# Lenobitech_Schematic.net
KiCad netlist of a schematic drawn in Altium Designer
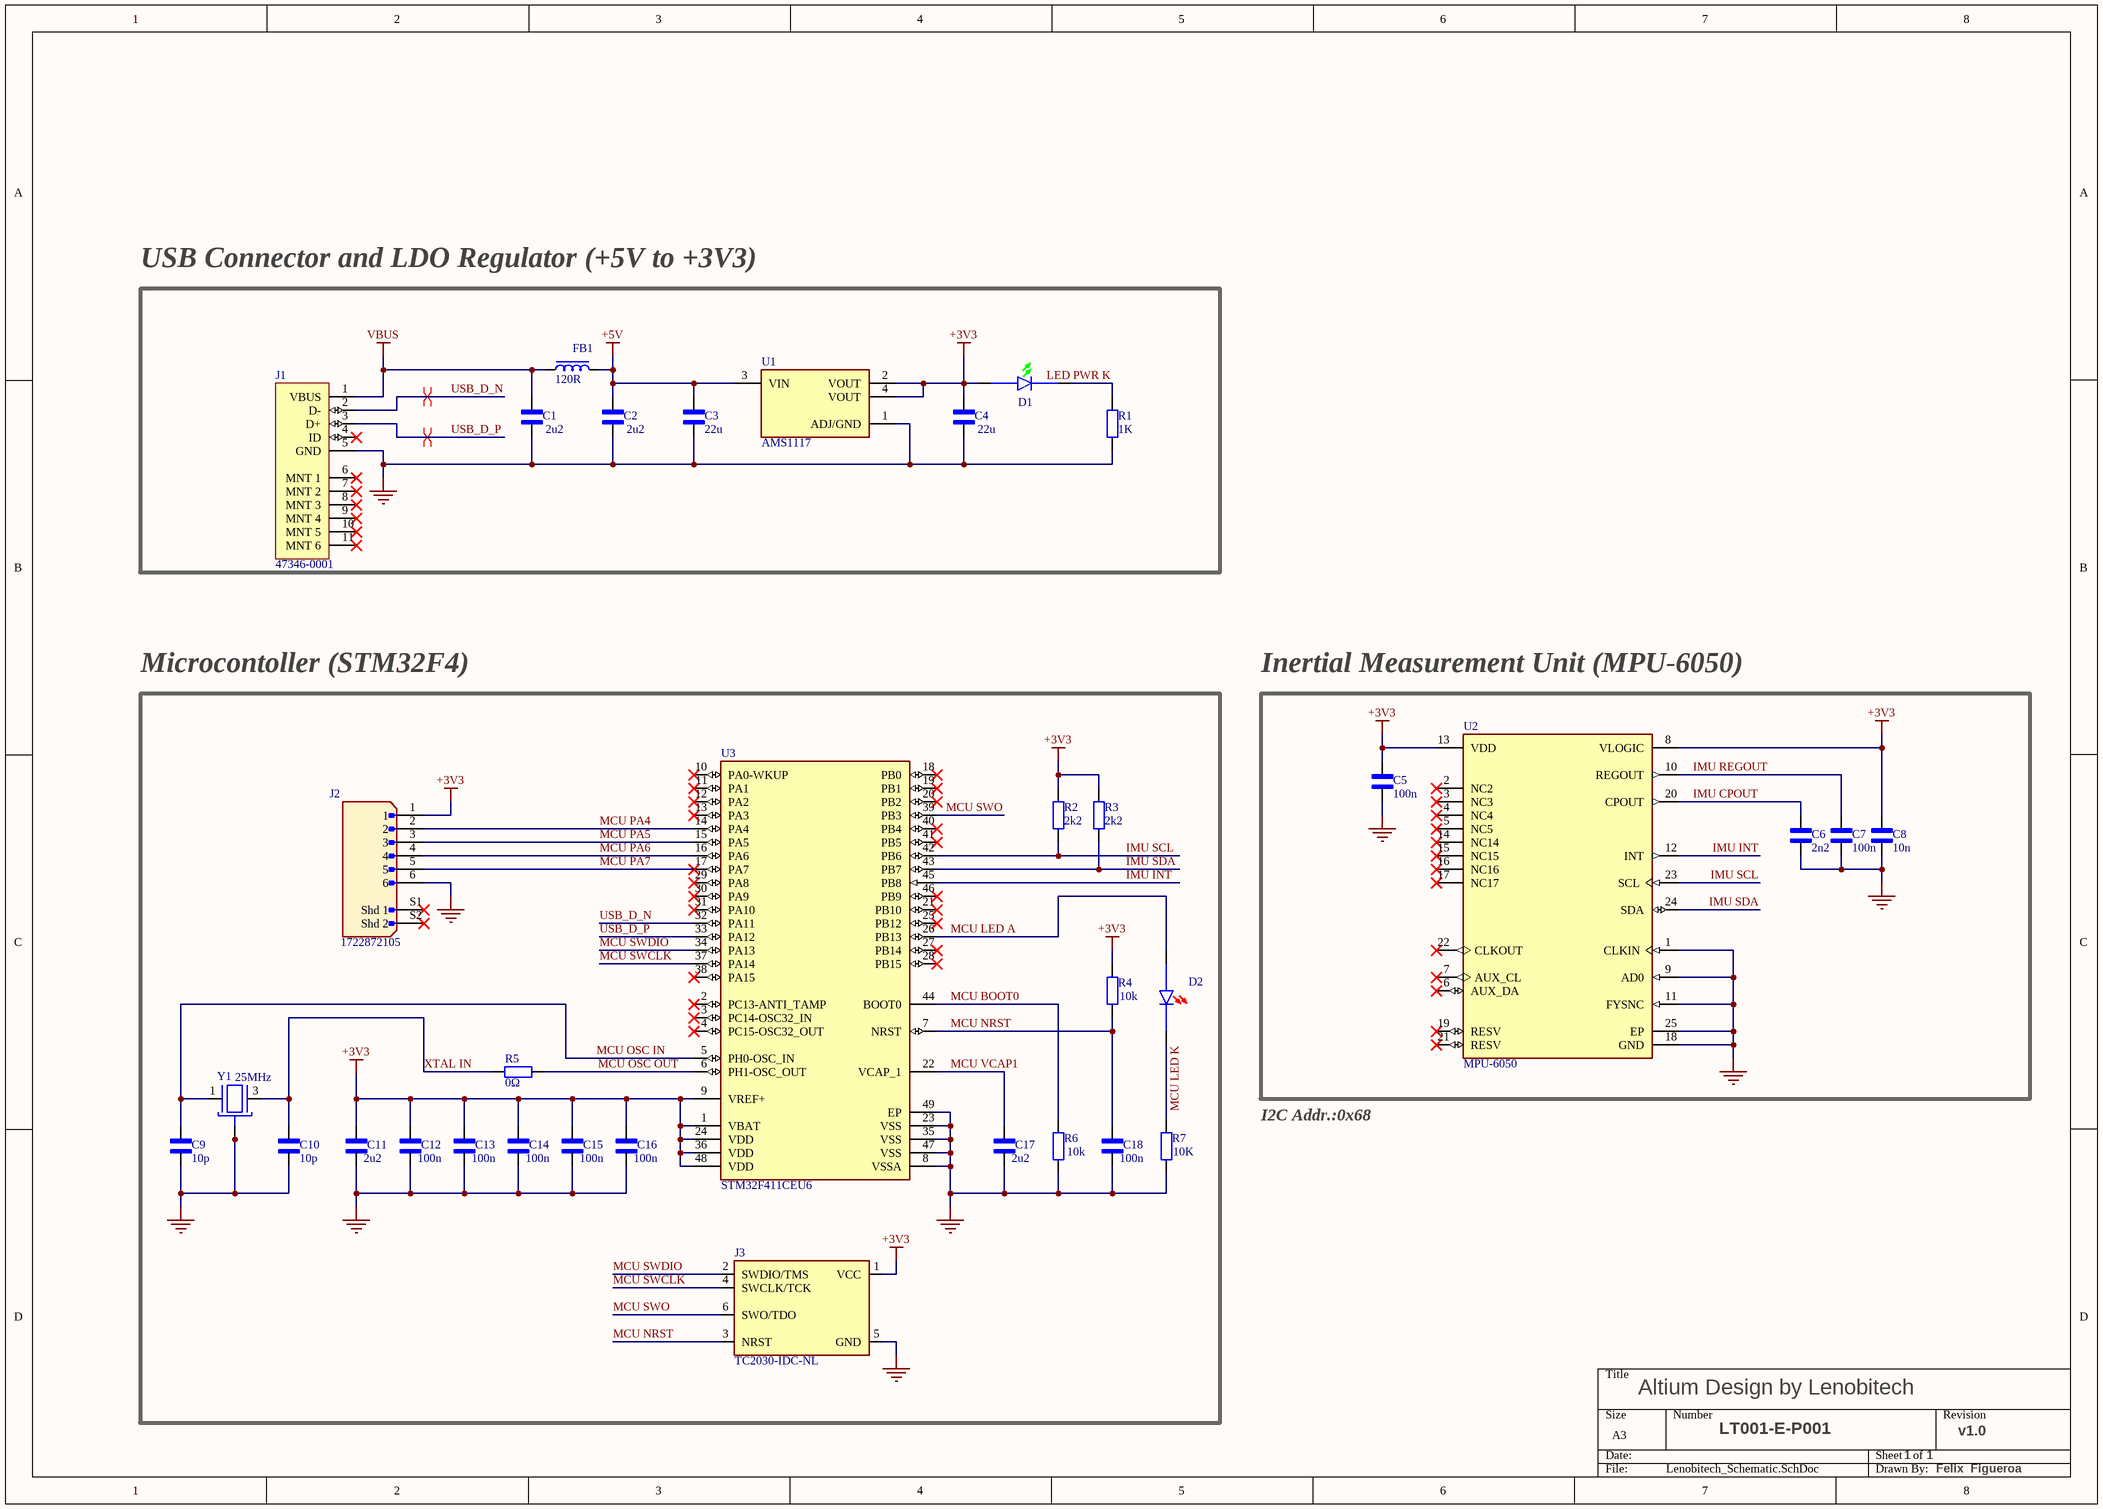
[diagram p0: Lenobitech_Schematic.SchDoc]

(export (version "E")
  (design (tool "Eeschema 10.0.6"))
  (components
    (comp (ref "C1")
      (value "2u2")
      (footprint "CAPC1608X90N")
      (description "C0603C225K4PACTU\r\n2.2碌F 卤10% 16V Ceramic Capacitor X5R 0603 _1608 Metric_")
      (fields (field (name "MF") "KEMET") (field (name "MP") "C0603C225K4PACTU"))
      (libsource (lib "Schlib_Lenobitech") (part "C0603_16V"))
    )
    (comp (ref "C2")
      (value "2u2")
      (footprint "CAPC1608X90N")
      (description "C0603C225K4PACTU\r\n2.2碌F 卤10% 16V Ceramic Capacitor X5R 0603 _1608 Metric_")
      (fields (field (name "MF") "KEMET") (field (name "MP") "C0603C225K4PACTU"))
      (libsource (lib "Schlib_Lenobitech") (part "CAP_0603_16V"))
    )
    (comp (ref "C3")
      (value "22u")
      (footprint "CAPC2012X145N")
      (description "C0805C226M8PAC7800\r\n22碌F 卤20% 16V Ceramic Capacitor X5R 0805 _2012 Metric_")
      (fields (field (name "MP") "C0805C226M8PAC7800") (field (name "DIGI-KEY_PART_NUMBER") "399-12069-1-ND"))
      (libsource (lib "Schlib_Lenobitech") (part "CAP_0805_16V"))
    )
    (comp (ref "C4")
      (value "22u")
      (footprint "CAPC2012X145N")
      (description "C0805C226M8PAC7800\r\n22碌F 卤20% 16V Ceramic Capacitor X5R 0805 _2012 Metric_")
      (fields (field (name "MF") "KEMET") (field (name "MP") "C0805C226M8PAC7800"))
      (libsource (lib "Schlib_Lenobitech") (part "CAP_0805_16V"))
    )
    (comp (ref "C5")
      (value "100n")
      (footprint "CAPC1005X55N")
      (description "C0402C104K4RAC7411_KEMET\r\n0.1碌F 卤10% 16V Ceramic Capacitor X7R 0402 (1005 Metric)")
      (fields (field (name "MP") "C0402C104K4RAC7411") (field (name "MF") "KEMET"))
      (libsource (lib "Schlib_Lenobitech") (part "CAP_0402_16V"))
    )
    (comp (ref "C6")
      (value "2n2")
      (footprint "CAPC1005X55N")
      (description "C0402C104K4RAC7411_KEMET\r\n0.1碌F 卤10% 16V Ceramic Capacitor X7R 0402 (1005 Metric)")
      (fields (field (name "MP") "C0402C104K4RAC7411") (field (name "MF") "KEMET"))
      (libsource (lib "") (part "CAP_0402_16V_1"))
    )
    (comp (ref "C7")
      (value "100n")
      (footprint "CAPC1005X55N")
      (description "C0402C104K4RAC7411_KEMET\r\n0.1碌F 卤10% 16V Ceramic Capacitor X7R 0402 (1005 Metric)")
      (fields (field (name "MP") "C0402C104K4RAC7411") (field (name "MF") "KEMET"))
      (libsource (lib "") (part "CAP_0402_16V_1"))
    )
    (comp (ref "C8")
      (value "10n")
      (footprint "CAPC1005X55N")
      (description "C0402C104K4RAC7411_KEMET\r\n0.1碌F 卤10% 16V Ceramic Capacitor X7R 0402 (1005 Metric)")
      (fields (field (name "MP") "C0402C104K4RAC7411") (field (name "MF") "KEMET"))
      (libsource (lib "") (part "CAP_0402_16V_1"))
    )
    (comp (ref "C9")
      (value "10p")
      (footprint "CAPC1005X55N")
      (description "C0402C104K4RAC7411_KEMET\r\n0.1碌F 卤10% 16V Ceramic Capacitor X7R 0402 (1005 Metric)")
      (fields (field (name "MP") "C0402C104K4RAC7411") (field (name "MF") "KEMET"))
      (libsource (lib "Schlib_Lenobitech") (part "CAP_0402_16V"))
    )
    (comp (ref "C10")
      (value "10p")
      (footprint "CAPC1005X55N")
      (description "C0402C104K4RAC7411_KEMET\r\n0.1碌F 卤10% 16V Ceramic Capacitor X7R 0402 (1005 Metric)")
      (fields (field (name "MP") "C0402C104K4RAC7411") (field (name "MF") "KEMET"))
      (libsource (lib "Schlib_Lenobitech") (part "CAP_0402_16V"))
    )
    (comp (ref "C11")
      (value "2u2")
      (footprint "CAPC1608X90N")
      (description "C0603C225K4PACTU\r\n2.2碌F 卤10% 16V Ceramic Capacitor X5R 0603 _1608 Metric_")
      (fields (field (name "MF") "KEMET") (field (name "MP") "C0603C225K4PACTU"))
      (libsource (lib "Schlib_Lenobitech") (part "C0603_16V"))
    )
    (comp (ref "C12")
      (value "100n")
      (footprint "CAPC1005X55N")
      (description "C0402C104K4RAC7411_KEMET\r\n0.1碌F 卤10% 16V Ceramic Capacitor X7R 0402 (1005 Metric)")
      (fields (field (name "MP") "C0402C104K4RAC7411") (field (name "MF") "KEMET"))
      (libsource (lib "Schlib_Lenobitech") (part "C0402_16V"))
    )
    (comp (ref "C13")
      (value "100n")
      (footprint "CAPC1005X55N")
      (description "C0402C104K4RAC7411_KEMET\r\n0.1碌F 卤10% 16V Ceramic Capacitor X7R 0402 (1005 Metric)")
      (fields (field (name "MP") "C0402C104K4RAC7411") (field (name "MF") "KEMET"))
      (libsource (lib "Schlib_Lenobitech") (part "C0402_16V"))
    )
    (comp (ref "C14")
      (value "100n")
      (footprint "CAPC1005X55N")
      (description "C0402C104K4RAC7411_KEMET\r\n0.1碌F 卤10% 16V Ceramic Capacitor X7R 0402 (1005 Metric)")
      (fields (field (name "MP") "C0402C104K4RAC7411") (field (name "MF") "KEMET"))
      (libsource (lib "Schlib_Lenobitech") (part "C0402_16V"))
    )
    (comp (ref "C15")
      (value "100n")
      (footprint "CAPC1005X55N")
      (description "C0402C104K4RAC7411_KEMET\r\n0.1碌F 卤10% 16V Ceramic Capacitor X7R 0402 (1005 Metric)")
      (fields (field (name "MP") "C0402C104K4RAC7411") (field (name "MF") "KEMET"))
      (libsource (lib "Schlib_Lenobitech") (part "C0402_16V"))
    )
    (comp (ref "C16")
      (value "100n")
      (footprint "CAPC1005X55N")
      (description "C0402C104K4RAC7411_KEMET\r\n0.1碌F 卤10% 16V Ceramic Capacitor X7R 0402 (1005 Metric)")
      (fields (field (name "MP") "C0402C104K4RAC7411") (field (name "MF") "KEMET"))
      (libsource (lib "Schlib_Lenobitech") (part "C0402_16V"))
    )
    (comp (ref "C17")
      (value "2u2")
      (footprint "CAPC1608X90N")
      (description "C0603C225K4PACTU\r\n2.2碌F 卤10% 16V Ceramic Capacitor X5R 0603 _1608 Metric_")
      (fields (field (name "MF") "KEMET") (field (name "MP") "C0603C225K4PACTU"))
      (libsource (lib "Schlib_Lenobitech") (part "C0603_16V"))
    )
    (comp (ref "C18")
      (value "100n")
      (footprint "CAPC1005X55N")
      (description "C0402C104K4RAC7411_KEMET\r\n0.1碌F 卤10% 16V Ceramic Capacitor X7R 0402 (1005 Metric)")
      (fields (field (name "MP") "C0402C104K4RAC7411") (field (name "MF") "KEMET"))
      (libsource (lib "Schlib_Lenobitech") (part "C0402_16V"))
    )
    (comp (ref "D1")
      (value "HSMS-C190")
      (footprint "LEDM1608X80")
      (description "Red 626nm LED Indication - Discrete 2.1V 0603 _1608 Metric_")
      (fields (field (name "MF") "Broadcom Limited"))
      (libsource (lib "Schlib_Lenobitech") (part "HSMS-C190"))
    )
    (comp (ref "D2")
      (value "HSMS-C190_1")
      (footprint "LEDM1608X80")
      (description "Red 626nm LED Indication - Discrete 2.1V 0603 _1608 Metric_")
      (fields (field (name "MP") "HSMS-C190") (field (name "MF") "Broadcom Limited"))
      (libsource (lib "Schlib_Lenobitech") (part "HSMS-C190_RD"))
    )
    (comp (ref "FB1")
      (value "120R")
      (footprint "PcbLib_Lenobitech:BEADC1608X75N")
      (description "1 kOhms @ 100MHz 1 G眉莽 Hatt谋 Ferrit Boncuk 0603 (1608 Metrik) 800mA 230mOhm")
      (fields (field (name "MP") "BLM18KG102WH1D") (field (name "MF") "Murata"))
      (libsource (lib "Schlib_Lenobitech") (part "BLM18KG102WH1D"))
    )
    (comp (ref "J1")
      (value "47346-0001")
      (footprint "PcbLib_Lenobitech:MOLEX_47346-0001")
      (description "USB Connectors MICRO USB B RECPT BTTM MOUNT ASSY")
      (fields (field (name "MF") "Molex"))
      (libsource (lib "Schlib_Lenobitech") (part "47346-0001"))
    )
    (comp (ref "J2")
      (value "1722872105")
      (footprint "JST_SM06B-SRSS-TB(LF)(SN)")
      (description "Connector Header Surface Mount, Right Angle 6 position 0.039\" (1.00mm)")
      (libsource (lib "Schlib_Lenobitech") (part "SM06B-SRSS-TB"))
    )
    (comp (ref "J3")
      (value "TC2030-IDC-NL")
      (footprint "TAG_TC2030-IDC-NL")
      (description "CABLE ADAPTER 6 POS")
      (libsource (lib "Schlib_Lenobitech") (part "TC2030-IDC-NL"))
    )
    (comp (ref "R1")
      (value "1K")
      (footprint "RESC1005X37N")
      (description "AC0402 10K 5% 0,063W AUTOMO")
      (fields (field (name "MP") "AC0402JR-0710KL") (field (name "Comment") "RES_0402"))
      (libsource (lib "Schlib_Lenobitech") (part "RES_0402"))
    )
    (comp (ref "R2")
      (value "2k2")
      (footprint "RESC1005X37N")
      (description "AC0402 10K 5% 0,063W AUTOMO")
      (fields (field (name "MP") "AC0402JR-0710KL") (field (name "Comment") "RES_0402"))
      (libsource (lib "Schlib_Lenobitech") (part "RES_0402"))
    )
    (comp (ref "R3")
      (value "2k2")
      (footprint "RESC1005X37N")
      (description "AC0402 10K 5% 0,063W AUTOMO")
      (fields (field (name "MP") "AC0402JR-0710KL") (field (name "Comment") "RES_0402"))
      (libsource (lib "Schlib_Lenobitech") (part "RES_0402"))
    )
    (comp (ref "R4")
      (value "10k")
      (footprint "RESC1005X37N")
      (description "AC0402 10K 5% 0,063W AUTOMO")
      (fields (field (name "MP") "AC0402JR-0710KL") (field (name "Comment") "RES_0402"))
      (libsource (lib "Schlib_Lenobitech") (part "RES_0402"))
    )
    (comp (ref "R5")
      (value "0Ω")
      (footprint "RESC1005X37N")
      (description "AC0402 10K 5% 0,063W AUTOMO")
      (fields (field (name "MP") "AC0402JR-0710KL") (field (name "Comment") "RES_0402"))
      (libsource (lib "") (part "RES_0402_1"))
    )
    (comp (ref "R6")
      (value "10k")
      (footprint "RESC1005X37N")
      (description "AC0402 10K 5% 0,063W AUTOMO")
      (fields (field (name "MP") "AC0402JR-0710KL") (field (name "Comment") "RES_0402"))
      (libsource (lib "Schlib_Lenobitech") (part "RES_0402"))
    )
    (comp (ref "R7")
      (value "10K")
      (footprint "RESC1005X37N")
      (description "AC0402 10K 5% 0,063W AUTOMO")
      (fields (field (name "MP") "AC0402JR-0710KL") (field (name "Comment") "RES_0402"))
      (libsource (lib "") (part "RES_0402_2"))
    )
    (comp (ref "U1")
      (value "AMS1117")
      (footprint "SOT229P700X180-4N")
      (description "Sot223/Pkg 1-Amp 5-Volt Low Drop Out Voltage Regulatator")
      (libsource (lib "Schlib_Lenobitech") (part "AMS1117"))
    )
    (comp (ref "U2")
      (value "MPU-6050")
      (footprint "PcbLib_Lenobitech:IC_MPU6050")
      (fields (field (name "MP") "MPU6050"))
      (libsource (lib "Schlib_Lenobitech") (part "MPU6050"))
    )
    (comp (ref "U3")
      (value "STM32F411CEU6")
      (footprint "PcbLib_Lenobitech:QFN50P700X700X60-49N")
      (description "ARMÂ® CortexÂ®-M4 STM32F4 Microcontroller IC 32-Bit 100MHz 512KB (512K x 8) FLASH 48-UFQFPN (7x7)")
      (fields (field (name "MF") "STMicroelectronics"))
      (libsource (lib "Schlib_Lenobitech") (part "STM32F411CEU6"))
    )
    (comp (ref "Y1")
      (value "25MHz")
      (footprint "OSC_ABM3B-25.000MHZ-10-1-U-T")
      (description "25 MHz Â±10ppm Crystal 10pF 50 Ohms 4-SMD, No Lead")
      (fields (field (name "MF") "Abracon") (field (name "MP") "ABM3B-25.000MHZ-10-1-U-T"))
      (libsource (lib "Schlib_Lenobitech") (part "ABM3B-25.000MHZ-10-1-U-T"))
    )
  )
  (nets
    (net (code "1") (name "+3V3") (class "Default")
      (node (ref "C11") (pin "2") (pinfunction "2_2") (pintype "passive"))
      (node (ref "C12") (pin "2") (pinfunction "2_2") (pintype "passive"))
      (node (ref "C13") (pin "2") (pinfunction "2_2") (pintype "passive"))
      (node (ref "C14") (pin "2") (pinfunction "2_2") (pintype "passive"))
      (node (ref "C15") (pin "2") (pinfunction "2_2") (pintype "passive"))
      (node (ref "C16") (pin "2") (pinfunction "2_2") (pintype "passive"))
      (node (ref "C4") (pin "2") (pinfunction "2_2") (pintype "passive"))
      (node (ref "C5") (pin "2") (pinfunction "2_2") (pintype "passive"))
      (node (ref "C8") (pin "1") (pinfunction "1_1") (pintype "passive"))
      (node (ref "D1") (pin "A") (pinfunction "A_A") (pintype "passive"))
      (node (ref "J2") (pin "1") (pinfunction "1_1") (pintype "passive"))
      (node (ref "J3") (pin "1") (pinfunction "VCC_1") (pintype "passive"))
      (node (ref "R2") (pin "2") (pinfunction "2_2") (pintype "passive"))
      (node (ref "R3") (pin "2") (pinfunction "2_2") (pintype "passive"))
      (node (ref "R4") (pin "2") (pinfunction "2_2") (pintype "passive"))
      (node (ref "U1") (pin "2") (pinfunction "VOUT_2") (pintype "passive"))
      (node (ref "U1") (pin "4") (pinfunction "VOUT_4") (pintype "passive"))
      (node (ref "U2") (pin "13") (pinfunction "VDD_13") (pintype "power_in"))
      (node (ref "U2") (pin "8") (pinfunction "VLOGIC_8") (pintype "power_in"))
      (node (ref "U3") (pin "1") (pinfunction "VBAT_1") (pintype "passive"))
      (node (ref "U3") (pin "24") (pinfunction "VDD_24") (pintype "passive"))
      (node (ref "U3") (pin "36") (pinfunction "VDD_36") (pintype "passive"))
      (node (ref "U3") (pin "48") (pinfunction "VDD_48") (pintype "passive"))
      (node (ref "U3") (pin "9") (pinfunction "VREF+_9") (pintype "passive"))
    )
    (net (code "2") (name "+5V") (class "Default")
      (node (ref "C2") (pin "2") (pinfunction "2_2") (pintype "passive"))
      (node (ref "C3") (pin "2") (pinfunction "2_2") (pintype "passive"))
      (node (ref "FB1") (pin "2") (pinfunction "2_2") (pintype "passive"))
      (node (ref "U1") (pin "3") (pinfunction "VIN_3") (pintype "passive"))
    )
    (net (code "3") (name "/IMU CPOUT") (class "Default")
      (node (ref "C6") (pin "1") (pinfunction "1_1") (pintype "passive"))
      (node (ref "U2") (pin "20") (pinfunction "CPOUT_20") (pintype "output"))
    )
    (net (code "4") (name "/IMU INT") (class "Default")
      (node (ref "U2") (pin "12") (pinfunction "INT_12") (pintype "output"))
      (node (ref "U3") (pin "45") (pinfunction "PB8_45") (pintype "input"))
    )
    (net (code "5") (name "/IMU REGOUT") (class "Default")
      (node (ref "C7") (pin "1") (pinfunction "1_1") (pintype "passive"))
      (node (ref "U2") (pin "10") (pinfunction "REGOUT_10") (pintype "output"))
    )
    (net (code "6") (name "/IMU SCL") (class "Default")
      (node (ref "R2") (pin "1") (pinfunction "1_1") (pintype "passive"))
      (node (ref "U2") (pin "23") (pinfunction "SCL_23") (pintype "input"))
      (node (ref "U3") (pin "42") (pinfunction "PB6_42") (pintype "bidirectional"))
    )
    (net (code "7") (name "/IMU SDA") (class "Default")
      (node (ref "R3") (pin "1") (pinfunction "1_1") (pintype "passive"))
      (node (ref "U2") (pin "24") (pinfunction "SDA_24") (pintype "bidirectional"))
      (node (ref "U3") (pin "43") (pinfunction "PB7_43") (pintype "bidirectional"))
    )
    (net (code "8") (name "/LED PWR K") (class "Default")
      (node (ref "D1") (pin "K") (pinfunction "K_K") (pintype "passive"))
      (node (ref "R1") (pin "2") (pinfunction "2_2") (pintype "passive"))
    )
    (net (code "9") (name "/MCU BOOT0") (class "Default")
      (node (ref "R6") (pin "2") (pinfunction "2_2") (pintype "passive"))
      (node (ref "U3") (pin "44") (pinfunction "BOOT0_44") (pintype "passive"))
    )
    (net (code "10") (name "/MCU LED A") (class "Default")
      (node (ref "D2") (pin "A") (pinfunction "A_A") (pintype "passive"))
      (node (ref "U3") (pin "26") (pinfunction "PB13_26") (pintype "bidirectional"))
    )
    (net (code "11") (name "/MCU LED K") (class "Default")
      (node (ref "D2") (pin "K") (pinfunction "K_K") (pintype "passive"))
      (node (ref "R7") (pin "1") (pinfunction "1_1") (pintype "passive"))
    )
    (net (code "12") (name "/MCU NRST") (class "Default")
      (node (ref "C18") (pin "2") (pinfunction "2_2") (pintype "passive"))
      (node (ref "J3") (pin "3") (pinfunction "NRST_3") (pintype "passive"))
      (node (ref "R4") (pin "1") (pinfunction "1_1") (pintype "passive"))
      (node (ref "U3") (pin "7") (pinfunction "NRST_7") (pintype "bidirectional"))
    )
    (net (code "13") (name "/MCU OSC IN") (class "Default")
      (node (ref "C9") (pin "2") (pinfunction "2_2") (pintype "passive"))
      (node (ref "U3") (pin "5") (pinfunction "PH0-OSC_IN_5") (pintype "bidirectional"))
      (node (ref "Y1") (pin "1") (pinfunction "1_1") (pintype "passive"))
    )
    (net (code "14") (name "/MCU OSC OUT") (class "Default")
      (node (ref "R5") (pin "1") (pinfunction "1_1") (pintype "passive"))
      (node (ref "U3") (pin "6") (pinfunction "PH1-OSC_OUT_6") (pintype "bidirectional"))
    )
    (net (code "15") (name "/MCU PA4") (class "Default")
      (node (ref "J2") (pin "2") (pinfunction "2_2") (pintype "passive"))
      (node (ref "U3") (pin "14") (pinfunction "PA4_14") (pintype "bidirectional"))
    )
    (net (code "16") (name "/MCU PA5") (class "Default")
      (node (ref "J2") (pin "3") (pinfunction "3_3") (pintype "passive"))
      (node (ref "U3") (pin "15") (pinfunction "PA5_15") (pintype "bidirectional"))
    )
    (net (code "17") (name "/MCU PA6") (class "Default")
      (node (ref "J2") (pin "4") (pinfunction "4_4") (pintype "passive"))
      (node (ref "U3") (pin "16") (pinfunction "PA6_16") (pintype "bidirectional"))
    )
    (net (code "18") (name "/MCU PA7") (class "Default")
      (node (ref "J2") (pin "5") (pinfunction "5_5") (pintype "passive"))
      (node (ref "U3") (pin "17") (pinfunction "PA7_17") (pintype "bidirectional"))
    )
    (net (code "19") (name "/MCU SWCLK") (class "Default")
      (node (ref "J3") (pin "4") (pinfunction "SWCLK/TCK_4") (pintype "passive"))
      (node (ref "U3") (pin "37") (pinfunction "PA14_37") (pintype "bidirectional"))
    )
    (net (code "20") (name "/MCU SWDIO") (class "Default")
      (node (ref "J3") (pin "2") (pinfunction "SWDIO/TMS_2") (pintype "passive"))
      (node (ref "U3") (pin "34") (pinfunction "PA13_34") (pintype "bidirectional"))
    )
    (net (code "21") (name "/MCU SWO") (class "Default")
      (node (ref "J3") (pin "6") (pinfunction "SWO/TDO_6") (pintype "passive"))
      (node (ref "U3") (pin "39") (pinfunction "PB3_39") (pintype "bidirectional"))
    )
    (net (code "22") (name "/MCU VCAP1") (class "Default")
      (node (ref "C17") (pin "2") (pinfunction "2_2") (pintype "passive"))
      (node (ref "U3") (pin "22") (pinfunction "VCAP_1_22") (pintype "power_in"))
    )
    (net (code "23") (name "/USB_D_N") (class "Default")
      (node (ref "J1") (pin "2") (pinfunction "D-_2") (pintype "bidirectional"))
      (node (ref "U3") (pin "32") (pinfunction "PA11_32") (pintype "bidirectional"))
    )
    (net (code "24") (name "/USB_D_P") (class "Default")
      (node (ref "J1") (pin "3") (pinfunction "D+_3") (pintype "bidirectional"))
      (node (ref "U3") (pin "33") (pinfunction "PA12_33") (pintype "bidirectional"))
    )
    (net (code "25") (name "/XTAL IN") (class "Default")
      (node (ref "C10") (pin "2") (pinfunction "2_2") (pintype "passive"))
      (node (ref "R5") (pin "2") (pinfunction "2_2") (pintype "passive"))
      (node (ref "Y1") (pin "3") (pinfunction "3_3") (pintype "passive"))
    )
    (net (code "26") (name "GND") (class "Default")
      (node (ref "C1") (pin "1") (pinfunction "1_1") (pintype "passive"))
      (node (ref "C10") (pin "1") (pinfunction "1_1") (pintype "passive"))
      (node (ref "C11") (pin "1") (pinfunction "1_1") (pintype "passive"))
      (node (ref "C12") (pin "1") (pinfunction "1_1") (pintype "passive"))
      (node (ref "C13") (pin "1") (pinfunction "1_1") (pintype "passive"))
      (node (ref "C14") (pin "1") (pinfunction "1_1") (pintype "passive"))
      (node (ref "C15") (pin "1") (pinfunction "1_1") (pintype "passive"))
      (node (ref "C16") (pin "1") (pinfunction "1_1") (pintype "passive"))
      (node (ref "C17") (pin "1") (pinfunction "1_1") (pintype "passive"))
      (node (ref "C18") (pin "1") (pinfunction "1_1") (pintype "passive"))
      (node (ref "C2") (pin "1") (pinfunction "1_1") (pintype "passive"))
      (node (ref "C3") (pin "1") (pinfunction "1_1") (pintype "passive"))
      (node (ref "C4") (pin "1") (pinfunction "1_1") (pintype "passive"))
      (node (ref "C5") (pin "1") (pinfunction "1_1") (pintype "passive"))
      (node (ref "C6") (pin "2") (pinfunction "2_2") (pintype "passive"))
      (node (ref "C7") (pin "2") (pinfunction "2_2") (pintype "passive"))
      (node (ref "C8") (pin "2") (pinfunction "2_2") (pintype "passive"))
      (node (ref "C9") (pin "1") (pinfunction "1_1") (pintype "passive"))
      (node (ref "J1") (pin "5") (pinfunction "GND_5") (pintype "power_in"))
      (node (ref "J2") (pin "6") (pinfunction "6_6") (pintype "passive"))
      (node (ref "J3") (pin "5") (pinfunction "GND_5") (pintype "passive"))
      (node (ref "R1") (pin "1") (pinfunction "1_1") (pintype "passive"))
      (node (ref "R6") (pin "1") (pinfunction "1_1") (pintype "passive"))
      (node (ref "R7") (pin "2") (pinfunction "2_2") (pintype "passive"))
      (node (ref "U1") (pin "1") (pinfunction "ADJ/GND_1") (pintype "power_in"))
      (node (ref "U2") (pin "1") (pinfunction "CLKIN_1") (pintype "input"))
      (node (ref "U2") (pin "11") (pinfunction "FYSNC_11") (pintype "input"))
      (node (ref "U2") (pin "18") (pinfunction "GND_18") (pintype "power_in"))
      (node (ref "U2") (pin "25") (pinfunction "EP_25") (pintype "power_in"))
      (node (ref "U2") (pin "9") (pinfunction "AD0_9") (pintype "input"))
      (node (ref "U3") (pin "23") (pinfunction "VSS_23") (pintype "power_in"))
      (node (ref "U3") (pin "35") (pinfunction "VSS_35") (pintype "power_in"))
      (node (ref "U3") (pin "47") (pinfunction "VSS_47") (pintype "power_in"))
      (node (ref "U3") (pin "49") (pinfunction "EP_49") (pintype "power_in"))
      (node (ref "U3") (pin "8") (pinfunction "VSSA_8") (pintype "power_in"))
      (node (ref "Y1") (pin "2") (pinfunction "GND_2") (pintype "power_in"))
      (node (ref "Y1") (pin "4") (pinfunction "GND_4") (pintype "power_in"))
    )
    (net (code "27") (name "VBUS") (class "Default")
      (node (ref "C1") (pin "2") (pinfunction "2_2") (pintype "passive"))
      (node (ref "FB1") (pin "1") (pinfunction "1_1") (pintype "passive"))
      (node (ref "J1") (pin "1") (pinfunction "VBUS_1") (pintype "power_in"))
    )
    (net (code "28") (name "unconnected-(J1-ID-Pad4)") (class "Default")
      (node (ref "J1") (pin "4") (pinfunction "ID_4") (pintype "bidirectional+no_connect"))
    )
    (net (code "29") (name "unconnected-(J1-MNT_1-Pad6)") (class "Default")
      (node (ref "J1") (pin "6") (pinfunction "MNT_1_6") (pintype "passive+no_connect"))
    )
    (net (code "30") (name "unconnected-(J1-MNT_2-Pad7)") (class "Default")
      (node (ref "J1") (pin "7") (pinfunction "MNT_2_7") (pintype "passive+no_connect"))
    )
    (net (code "31") (name "unconnected-(J1-MNT_3-Pad8)") (class "Default")
      (node (ref "J1") (pin "8") (pinfunction "MNT_3_8") (pintype "passive+no_connect"))
    )
    (net (code "32") (name "unconnected-(J1-MNT_4-Pad9)") (class "Default")
      (node (ref "J1") (pin "9") (pinfunction "MNT_4_9") (pintype "passive+no_connect"))
    )
    (net (code "33") (name "unconnected-(J1-MNT_5-Pad10)") (class "Default")
      (node (ref "J1") (pin "10") (pinfunction "MNT_5_10") (pintype "passive+no_connect"))
    )
    (net (code "34") (name "unconnected-(J1-MNT_6-Pad11)") (class "Default")
      (node (ref "J1") (pin "11") (pinfunction "MNT_6_11") (pintype "passive+no_connect"))
    )
    (net (code "35") (name "unconnected-(J2-Shd_1-PadS1)") (class "Default")
      (node (ref "J2") (pin "S1") (pinfunction "Shd_1_S1") (pintype "passive+no_connect"))
    )
    (net (code "36") (name "unconnected-(J2-Shd_2-PadS2)") (class "Default")
      (node (ref "J2") (pin "S2") (pinfunction "Shd_2_S2") (pintype "passive+no_connect"))
    )
    (net (code "37") (name "unconnected-(U2-AUX_CL-Pad7)") (class "Default")
      (node (ref "U2") (pin "7") (pinfunction "AUX_CL_7") (pintype "output+no_connect"))
    )
    (net (code "38") (name "unconnected-(U2-AUX_DA-Pad6)") (class "Default")
      (node (ref "U2") (pin "6") (pinfunction "AUX_DA_6") (pintype "bidirectional+no_connect"))
    )
    (net (code "39") (name "unconnected-(U2-CLKOUT-Pad22)") (class "Default")
      (node (ref "U2") (pin "22") (pinfunction "CLKOUT_22") (pintype "output+no_connect"))
    )
    (net (code "40") (name "unconnected-(U2-NC2-Pad2)") (class "Default")
      (node (ref "U2") (pin "2") (pinfunction "NC2_2") (pintype "passive+no_connect"))
    )
    (net (code "41") (name "unconnected-(U2-NC3-Pad3)") (class "Default")
      (node (ref "U2") (pin "3") (pinfunction "NC3_3") (pintype "passive+no_connect"))
    )
    (net (code "42") (name "unconnected-(U2-NC4-Pad4)") (class "Default")
      (node (ref "U2") (pin "4") (pinfunction "NC4_4") (pintype "passive+no_connect"))
    )
    (net (code "43") (name "unconnected-(U2-NC5-Pad5)") (class "Default")
      (node (ref "U2") (pin "5") (pinfunction "NC5_5") (pintype "passive+no_connect"))
    )
    (net (code "44") (name "unconnected-(U2-NC14-Pad14)") (class "Default")
      (node (ref "U2") (pin "14") (pinfunction "NC14_14") (pintype "passive+no_connect"))
    )
    (net (code "45") (name "unconnected-(U2-NC15-Pad15)") (class "Default")
      (node (ref "U2") (pin "15") (pinfunction "NC15_15") (pintype "passive+no_connect"))
    )
    (net (code "46") (name "unconnected-(U2-NC16-Pad16)") (class "Default")
      (node (ref "U2") (pin "16") (pinfunction "NC16_16") (pintype "passive+no_connect"))
    )
    (net (code "47") (name "unconnected-(U2-NC17-Pad17)") (class "Default")
      (node (ref "U2") (pin "17") (pinfunction "NC17_17") (pintype "passive+no_connect"))
    )
    (net (code "48") (name "unconnected-(U2-RESV-Pad19)") (class "Default")
      (node (ref "U2") (pin "19") (pinfunction "RESV_19") (pintype "bidirectional+no_connect"))
    )
    (net (code "49") (name "unconnected-(U2-RESV-Pad21)") (class "Default")
      (node (ref "U2") (pin "21") (pinfunction "RESV_21") (pintype "bidirectional+no_connect"))
    )
    (net (code "50") (name "unconnected-(U3-PA0-WKUP-Pad10)") (class "Default")
      (node (ref "U3") (pin "10") (pinfunction "PA0-WKUP_10") (pintype "bidirectional+no_connect"))
    )
    (net (code "51") (name "unconnected-(U3-PA1-Pad11)") (class "Default")
      (node (ref "U3") (pin "11") (pinfunction "PA1_11") (pintype "bidirectional+no_connect"))
    )
    (net (code "52") (name "unconnected-(U3-PA2-Pad12)") (class "Default")
      (node (ref "U3") (pin "12") (pinfunction "PA2_12") (pintype "bidirectional+no_connect"))
    )
    (net (code "53") (name "unconnected-(U3-PA3-Pad13)") (class "Default")
      (node (ref "U3") (pin "13") (pinfunction "PA3_13") (pintype "bidirectional+no_connect"))
    )
    (net (code "54") (name "unconnected-(U3-PA8-Pad29)") (class "Default")
      (node (ref "U3") (pin "29") (pinfunction "PA8_29") (pintype "bidirectional+no_connect"))
    )
    (net (code "55") (name "unconnected-(U3-PA9-Pad30)") (class "Default")
      (node (ref "U3") (pin "30") (pinfunction "PA9_30") (pintype "bidirectional+no_connect"))
    )
    (net (code "56") (name "unconnected-(U3-PA10-Pad31)") (class "Default")
      (node (ref "U3") (pin "31") (pinfunction "PA10_31") (pintype "bidirectional+no_connect"))
    )
    (net (code "57") (name "unconnected-(U3-PA15-Pad38)") (class "Default")
      (node (ref "U3") (pin "38") (pinfunction "PA15_38") (pintype "bidirectional+no_connect"))
    )
    (net (code "58") (name "unconnected-(U3-PB0-Pad18)") (class "Default")
      (node (ref "U3") (pin "18") (pinfunction "PB0_18") (pintype "bidirectional+no_connect"))
    )
    (net (code "59") (name "unconnected-(U3-PB1-Pad19)") (class "Default")
      (node (ref "U3") (pin "19") (pinfunction "PB1_19") (pintype "bidirectional+no_connect"))
    )
    (net (code "60") (name "unconnected-(U3-PB2-Pad20)") (class "Default")
      (node (ref "U3") (pin "20") (pinfunction "PB2_20") (pintype "bidirectional+no_connect"))
    )
    (net (code "61") (name "unconnected-(U3-PB4-Pad40)") (class "Default")
      (node (ref "U3") (pin "40") (pinfunction "PB4_40") (pintype "bidirectional+no_connect"))
    )
    (net (code "62") (name "unconnected-(U3-PB5-Pad41)") (class "Default")
      (node (ref "U3") (pin "41") (pinfunction "PB5_41") (pintype "bidirectional+no_connect"))
    )
    (net (code "63") (name "unconnected-(U3-PB9-Pad46)") (class "Default")
      (node (ref "U3") (pin "46") (pinfunction "PB9_46") (pintype "bidirectional+no_connect"))
    )
    (net (code "64") (name "unconnected-(U3-PB10-Pad21)") (class "Default")
      (node (ref "U3") (pin "21") (pinfunction "PB10_21") (pintype "bidirectional+no_connect"))
    )
    (net (code "65") (name "unconnected-(U3-PB12-Pad25)") (class "Default")
      (node (ref "U3") (pin "25") (pinfunction "PB12_25") (pintype "bidirectional+no_connect"))
    )
    (net (code "66") (name "unconnected-(U3-PB14-Pad27)") (class "Default")
      (node (ref "U3") (pin "27") (pinfunction "PB14_27") (pintype "bidirectional+no_connect"))
    )
    (net (code "67") (name "unconnected-(U3-PB15-Pad28)") (class "Default")
      (node (ref "U3") (pin "28") (pinfunction "PB15_28") (pintype "bidirectional+no_connect"))
    )
    (net (code "68") (name "unconnected-(U3-PC13-ANTI_TAMP-Pad2)") (class "Default")
      (node (ref "U3") (pin "2") (pinfunction "PC13-ANTI_TAMP_2") (pintype "bidirectional+no_connect"))
    )
    (net (code "69") (name "unconnected-(U3-PC14-OSC32_IN-Pad3)") (class "Default")
      (node (ref "U3") (pin "3") (pinfunction "PC14-OSC32_IN_3") (pintype "bidirectional+no_connect"))
    )
    (net (code "70") (name "unconnected-(U3-PC15-OSC32_OUT-Pad4)") (class "Default")
      (node (ref "U3") (pin "4") (pinfunction "PC15-OSC32_OUT_4") (pintype "bidirectional+no_connect"))
    )
  )
)
